# main_v11.net
KiCad netlist of a schematic drawn in Altium Designer
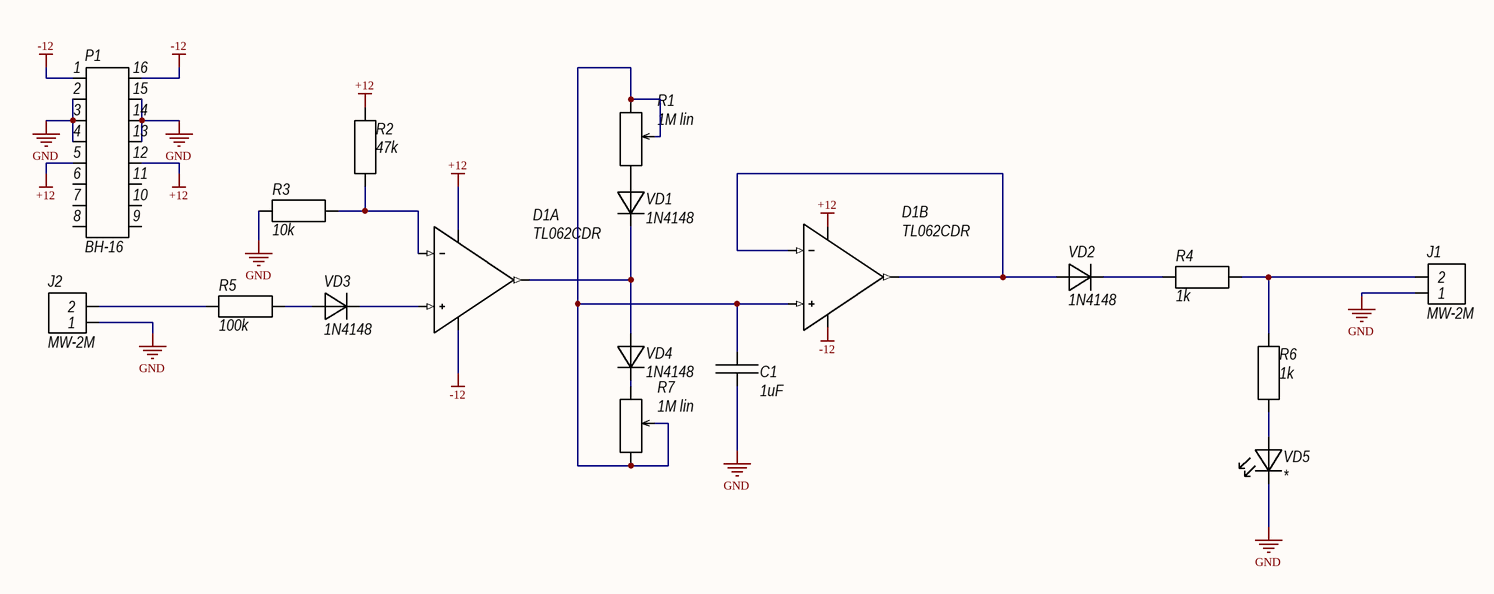
[diagram p0: main_v11.SchDoc]

(export (version "E")
  (design (tool "Eeschema 10.0.6"))
  (components
    (comp (ref "C1") (value "1uF") (footprint "CAP DISK 5mm") (libsource (lib "Schlib1") (part "Capacitor")))
    (comp (ref "D1")
      (value "TL062CDR")
      (footprint "DIP-8")
      (fields (field (name "MANUFACTURER") "Texas Instruments"))
      (libsource (lib "Schlib1") (part "TL062"))
    )
    (comp (ref "J1") (value "MW-2M") (footprint "MW-2M") (libsource (lib "Schlib1") (part "MW-2M")))
    (comp (ref "J2") (value "MW-2M") (footprint "MW-2M") (libsource (lib "Schlib1") (part "MW-2M")))
    (comp (ref "P1") (value "BH-16") (footprint "BH-16") (libsource (lib "Schlib1") (part "BH-16")))
    (comp (ref "R1") (value "1M lin") (footprint "T93YA") (libsource (lib "") (part "Potentiometr_1")))
    (comp (ref "R2") (value "47k") (footprint "R1206") (libsource (lib "") (part "Resistor_1")))
    (comp (ref "R3") (value "10k") (footprint "R1206") (libsource (lib "Schlib1") (part "Resistor")))
    (comp (ref "R4") (value "1k") (footprint "R1206") (libsource (lib "Schlib1") (part "Resistor")))
    (comp (ref "R5") (value "100k") (footprint "R1206") (libsource (lib "Schlib1") (part "Resistor")))
    (comp (ref "R6") (value "1k") (footprint "R1206") (libsource (lib "") (part "Resistor_1")))
    (comp (ref "R7") (value "1M lin") (footprint "T93YA") (libsource (lib "Schlib1") (part "Potentiometr")))
    (comp (ref "VD1")
      (value "1N4148")
      (footprint "SOD-123")
      (description "DIODE GEN PURP 75V 150MA")
      (fields (field (name "MANUFACTURER") "Vishay Semiconductor Diodes Division"))
      (libsource (lib "Schlib1") (part "1N4148W-E3-18"))
    )
    (comp (ref "VD2")
      (value "1N4148")
      (footprint "SOD-123")
      (description "DIODE GEN PURP 75V 150MA")
      (fields (field (name "MANUFACTURER") "Vishay Semiconductor Diodes Division"))
      (libsource (lib "Schlib1") (part "1N4148W-E3-18"))
    )
    (comp (ref "VD3")
      (value "1N4148")
      (footprint "SOD-123")
      (description "DIODE GEN PURP 75V 150MA")
      (fields (field (name "MANUFACTURER") "Vishay Semiconductor Diodes Division"))
      (libsource (lib "Schlib1") (part "1N4148W-E3-18"))
    )
    (comp (ref "VD4")
      (value "1N4148")
      (footprint "SOD-123")
      (description "DIODE GEN PURP 75V 150MA")
      (fields (field (name "MANUFACTURER") "Vishay Semiconductor Diodes Division"))
      (libsource (lib "Schlib1") (part "1N4148W-E3-18"))
    )
    (comp (ref "VD5") (value "*") (footprint "LED-5mm") (libsource (lib "Schlib1") (part "LED")))
  )
  (nets
    (net (code "1") (name "+12") (class "Default")
      (node (ref "D1") (pin "8") (pinfunction "Vcc+_8") (pintype "power_in"))
      (node (ref "P1") (pin "12") (pinfunction "12_12") (pintype "passive"))
      (node (ref "P1") (pin "5") (pinfunction "5_5") (pintype "passive"))
      (node (ref "R2") (pin "2") (pintype "passive"))
    )
    (net (code "2") (name "-12") (class "Default")
      (node (ref "D1") (pin "4") (pinfunction "Vcc-_4") (pintype "power_in"))
      (node (ref "P1") (pin "1") (pinfunction "1_1") (pintype "passive"))
      (node (ref "P1") (pin "16") (pinfunction "16_16") (pintype "passive"))
    )
    (net (code "3") (name "GND") (class "Default")
      (node (ref "C1") (pin "1") (pintype "passive"))
      (node (ref "J1") (pin "1") (pinfunction "1_1") (pintype "passive"))
      (node (ref "J2") (pin "1") (pinfunction "1_1") (pintype "passive"))
      (node (ref "P1") (pin "13") (pinfunction "13_13") (pintype "passive"))
      (node (ref "P1") (pin "14") (pinfunction "14_14") (pintype "passive"))
      (node (ref "P1") (pin "15") (pinfunction "15_15") (pintype "passive"))
      (node (ref "P1") (pin "2") (pinfunction "2_2") (pintype "passive"))
      (node (ref "P1") (pin "3") (pinfunction "3_3") (pintype "passive"))
      (node (ref "P1") (pin "4") (pinfunction "4_4") (pintype "passive"))
      (node (ref "R3") (pin "1") (pintype "passive"))
      (node (ref "VD5") (pin "2") (pintype "passive"))
    )
    (net (code "4") (name "Net-(D1A-1IN+)") (class "Default")
      (node (ref "D1") (pin "3") (pinfunction "1IN+_3") (pintype "input"))
      (node (ref "VD3") (pin "2") (pintype "passive"))
    )
    (net (code "5") (name "Net-(D1A-1IN-)") (class "Default")
      (node (ref "D1") (pin "2") (pinfunction "1IN-_2") (pintype "input"))
      (node (ref "R2") (pin "1") (pintype "passive"))
      (node (ref "R3") (pin "2") (pintype "passive"))
    )
    (net (code "6") (name "Net-(D1A-1OUT)") (class "Default")
      (node (ref "D1") (pin "1") (pinfunction "1OUT_1") (pintype "output"))
      (node (ref "VD1") (pin "2") (pintype "passive"))
      (node (ref "VD4") (pin "1") (pintype "passive"))
    )
    (net (code "7") (name "Net-(D1B-2IN-)") (class "Default")
      (node (ref "D1") (pin "6") (pinfunction "2IN-_6") (pintype "input"))
      (node (ref "D1") (pin "7") (pinfunction "2OUT_7") (pintype "output"))
      (node (ref "VD2") (pin "1") (pintype "passive"))
    )
    (net (code "8") (name "Net-(D1B-21IN+)") (class "Default")
      (node (ref "C1") (pin "2") (pintype "passive"))
      (node (ref "D1") (pin "5") (pinfunction "21IN+_5") (pintype "input"))
      (node (ref "R1") (pin "1") (pintype "passive"))
      (node (ref "R1") (pin "2") (pintype "passive"))
      (node (ref "R7") (pin "2") (pintype "passive"))
      (node (ref "R7") (pin "3") (pintype "passive"))
    )
    (net (code "9") (name "Net-(J1-Pad2)") (class "Default")
      (node (ref "J1") (pin "2") (pinfunction "2_2") (pintype "passive"))
      (node (ref "R4") (pin "2") (pintype "passive"))
      (node (ref "R6") (pin "2") (pintype "passive"))
    )
    (net (code "10") (name "Net-(J2-Pad2)") (class "Default")
      (node (ref "J2") (pin "2") (pinfunction "2_2") (pintype "passive"))
      (node (ref "R5") (pin "1") (pintype "passive"))
    )
    (net (code "11") (name "Net-(R1-Pad3)") (class "Default")
      (node (ref "R1") (pin "3") (pintype "passive"))
      (node (ref "VD1") (pin "1") (pintype "passive"))
    )
    (net (code "12") (name "Net-(R4-Pad1)") (class "Default")
      (node (ref "R4") (pin "1") (pintype "passive"))
      (node (ref "VD2") (pin "2") (pintype "passive"))
    )
    (net (code "13") (name "Net-(R5-Pad2)") (class "Default")
      (node (ref "R5") (pin "2") (pintype "passive"))
      (node (ref "VD3") (pin "1") (pintype "passive"))
    )
    (net (code "14") (name "Net-(R6-Pad1)") (class "Default")
      (node (ref "R6") (pin "1") (pintype "passive"))
      (node (ref "VD5") (pin "1") (pintype "passive"))
    )
    (net (code "15") (name "Net-(R7-Pad1)") (class "Default")
      (node (ref "R7") (pin "1") (pintype "passive"))
      (node (ref "VD4") (pin "2") (pintype "passive"))
    )
    (net (code "16") (name "unconnected-(P1-Pad6)") (class "Default")
      (node (ref "P1") (pin "6") (pinfunction "6_6") (pintype "passive"))
    )
    (net (code "17") (name "unconnected-(P1-Pad7)") (class "Default")
      (node (ref "P1") (pin "7") (pinfunction "7_7") (pintype "passive"))
    )
    (net (code "18") (name "unconnected-(P1-Pad8)") (class "Default")
      (node (ref "P1") (pin "8") (pinfunction "8_8") (pintype "passive"))
    )
    (net (code "19") (name "unconnected-(P1-Pad9)") (class "Default")
      (node (ref "P1") (pin "9") (pinfunction "9_9") (pintype "passive"))
    )
    (net (code "20") (name "unconnected-(P1-Pad10)") (class "Default")
      (node (ref "P1") (pin "10") (pinfunction "10_10") (pintype "passive"))
    )
    (net (code "21") (name "unconnected-(P1-Pad11)") (class "Default")
      (node (ref "P1") (pin "11") (pinfunction "11_11") (pintype "passive"))
    )
  )
)
